# rescue_linea5photo.net
KiCad netlist of a schematic drawn in EAGLE
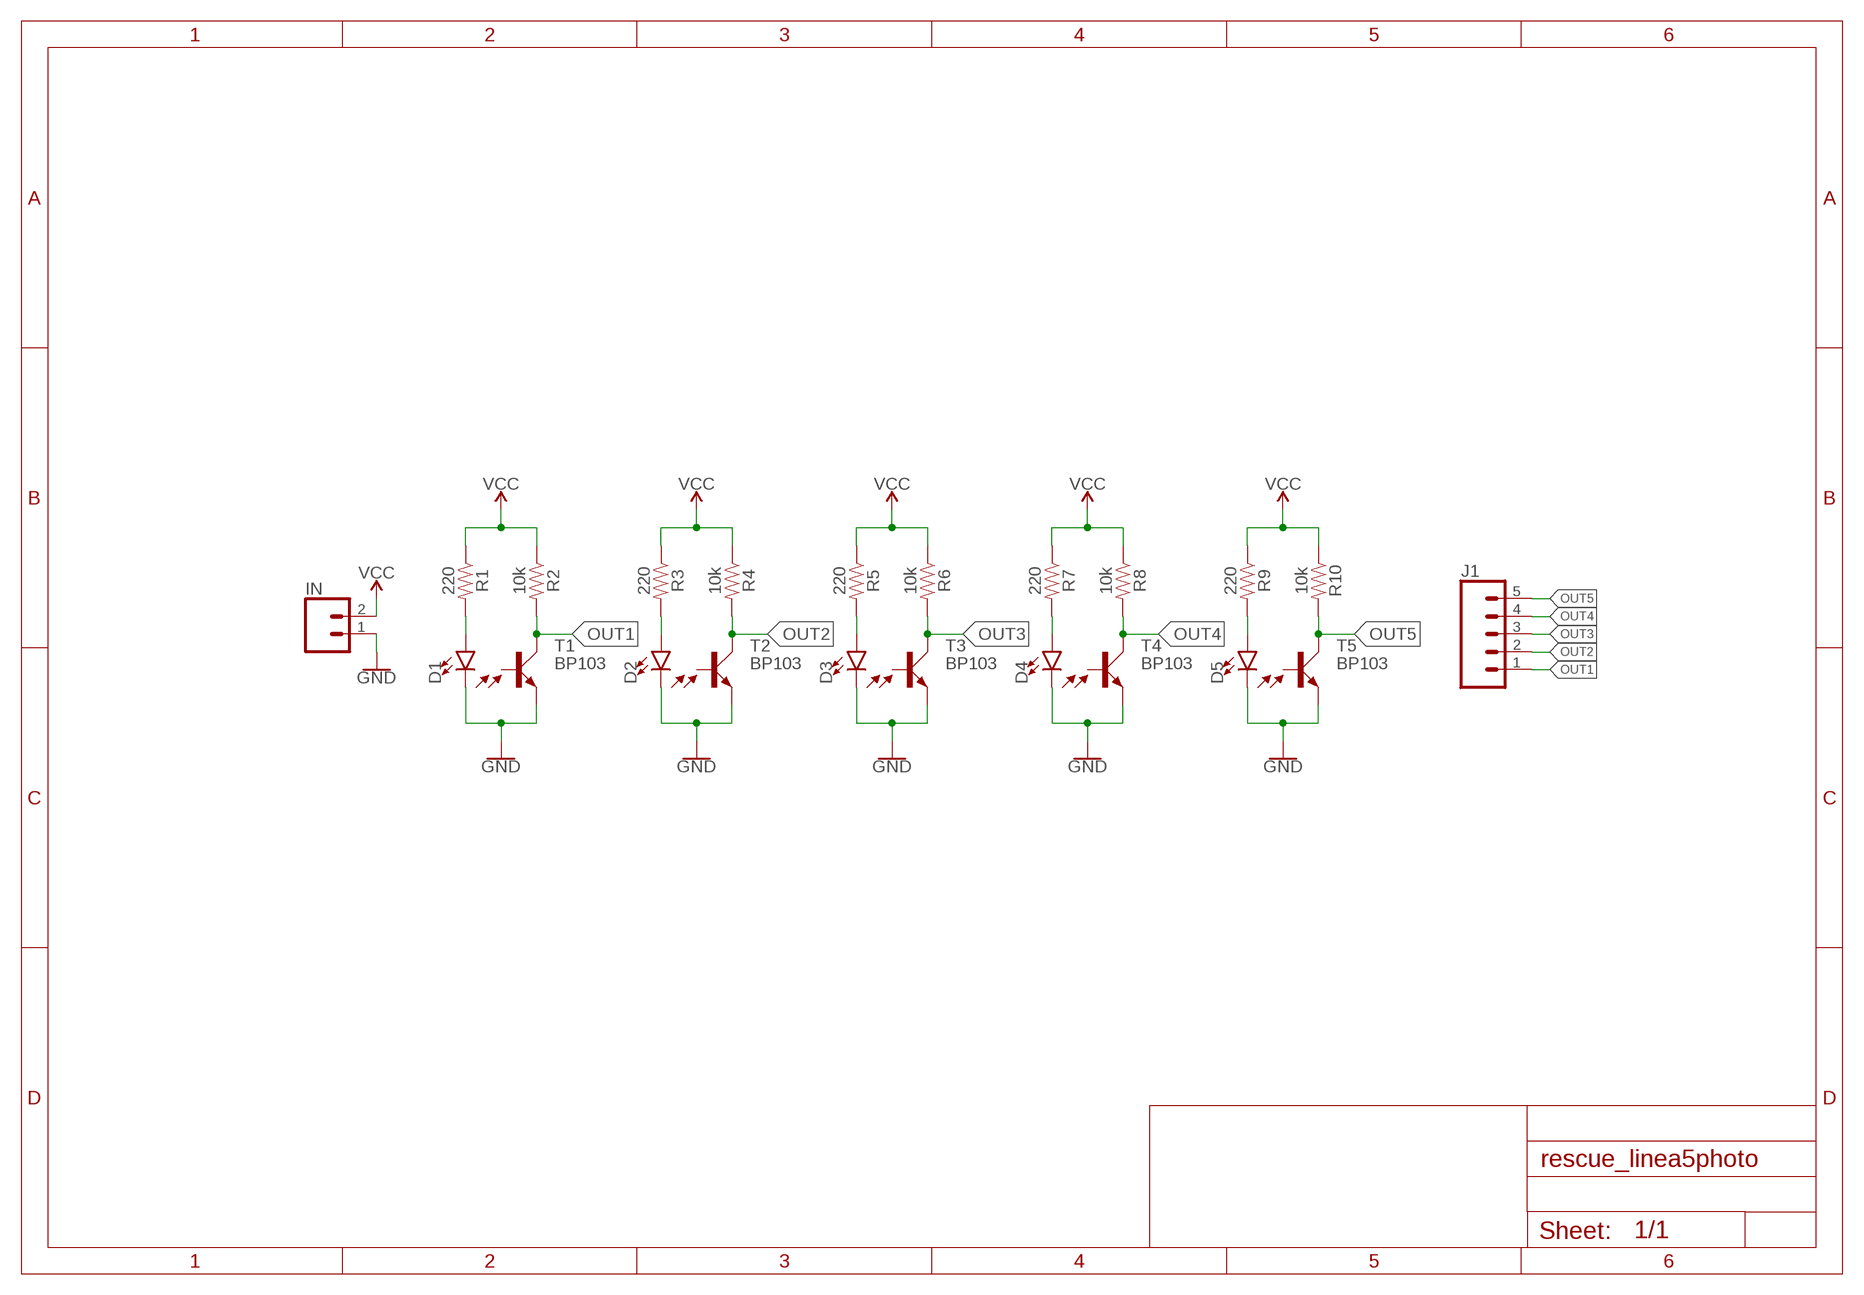
[diagram p0: schematic, sheet 1]

(export (version "E")
  (design (tool "Eeschema 10.0.6"))
  (components
    (comp (ref "D1")
      (value "LED5MM")
      (footprint "eagle-import:LED_5MM")
      (libsource (lib "eagle-import") (part "LED5MM"))
    )
    (comp (ref "D2")
      (value "LED5MM")
      (footprint "eagle-import:LED_5MM")
      (libsource (lib "eagle-import") (part "LED5MM"))
    )
    (comp (ref "D3")
      (value "LED5MM")
      (footprint "eagle-import:LED_5MM")
      (libsource (lib "eagle-import") (part "LED5MM"))
    )
    (comp (ref "D4")
      (value "LED5MM")
      (footprint "eagle-import:LED_5MM")
      (libsource (lib "eagle-import") (part "LED5MM"))
    )
    (comp (ref "D5")
      (value "LED5MM")
      (footprint "eagle-import:LED_5MM")
      (libsource (lib "eagle-import") (part "LED5MM"))
    )
    (comp (ref "IN")
      (value "CONN_02")
      (footprint "eagle-import:1X02")
      (libsource (lib "eagle-import") (part "CONN_02"))
    )
    (comp (ref "J1")
      (value "CONN_05")
      (footprint "eagle-import:1X05")
      (libsource (lib "eagle-import") (part "CONN_05"))
    )
    (comp (ref "R1")
      (value "220")
      (footprint "eagle-import:AXIAL-0.3")
      (libsource (lib "eagle-import") (part "RESISTORAXIAL-0.3"))
    )
    (comp (ref "R2")
      (value "10k")
      (footprint "eagle-import:AXIAL-0.3")
      (libsource (lib "eagle-import") (part "RESISTORAXIAL-0.3"))
    )
    (comp (ref "R3")
      (value "220")
      (footprint "eagle-import:AXIAL-0.3")
      (libsource (lib "eagle-import") (part "RESISTORAXIAL-0.3"))
    )
    (comp (ref "R4")
      (value "10k")
      (footprint "eagle-import:AXIAL-0.3")
      (libsource (lib "eagle-import") (part "RESISTORAXIAL-0.3"))
    )
    (comp (ref "R5")
      (value "220")
      (footprint "eagle-import:AXIAL-0.3")
      (libsource (lib "eagle-import") (part "RESISTORAXIAL-0.3"))
    )
    (comp (ref "R6")
      (value "10k")
      (footprint "eagle-import:AXIAL-0.3")
      (libsource (lib "eagle-import") (part "RESISTORAXIAL-0.3"))
    )
    (comp (ref "R7")
      (value "220")
      (footprint "eagle-import:AXIAL-0.3")
      (libsource (lib "eagle-import") (part "RESISTORAXIAL-0.3"))
    )
    (comp (ref "R8")
      (value "10k")
      (footprint "eagle-import:AXIAL-0.3")
      (libsource (lib "eagle-import") (part "RESISTORAXIAL-0.3"))
    )
    (comp (ref "R9")
      (value "220")
      (footprint "eagle-import:AXIAL-0.3")
      (libsource (lib "eagle-import") (part "RESISTORAXIAL-0.3"))
    )
    (comp (ref "R10")
      (value "10k")
      (footprint "eagle-import:AXIAL-0.3")
      (libsource (lib "eagle-import") (part "RESISTORAXIAL-0.3"))
    )
    (comp (ref "T1")
      (value "BP103")
      (footprint "eagle-import:BP103")
      (libsource (lib "eagle-import") (part "BP103"))
    )
    (comp (ref "T2")
      (value "BP103")
      (footprint "eagle-import:BP103")
      (libsource (lib "eagle-import") (part "BP103"))
    )
    (comp (ref "T3")
      (value "BP103")
      (footprint "eagle-import:BP103")
      (libsource (lib "eagle-import") (part "BP103"))
    )
    (comp (ref "T4")
      (value "BP103")
      (footprint "eagle-import:BP103")
      (libsource (lib "eagle-import") (part "BP103"))
    )
    (comp (ref "T5")
      (value "BP103")
      (footprint "eagle-import:BP103")
      (libsource (lib "eagle-import") (part "BP103"))
    )
  )
  (nets
    (net (code "1") (name "GND") (class "Default")
      (node (ref "D1") (pin "K") (pinfunction "C_K") (pintype "passive"))
      (node (ref "D2") (pin "K") (pinfunction "C_K") (pintype "passive"))
      (node (ref "D3") (pin "K") (pinfunction "C_K") (pintype "passive"))
      (node (ref "D4") (pin "K") (pinfunction "C_K") (pintype "passive"))
      (node (ref "D5") (pin "K") (pinfunction "C_K") (pintype "passive"))
      (node (ref "IN") (pin "1") (pinfunction "1_1") (pintype "passive"))
      (node (ref "T1") (pin "E") (pinfunction "E_E") (pintype "passive"))
      (node (ref "T2") (pin "E") (pinfunction "E_E") (pintype "passive"))
      (node (ref "T3") (pin "E") (pinfunction "E_E") (pintype "passive"))
      (node (ref "T4") (pin "E") (pinfunction "E_E") (pintype "passive"))
      (node (ref "T5") (pin "E") (pinfunction "E_E") (pintype "passive"))
    )
    (net (code "2") (name "Net-(R1-2)") (class "Default")
      (node (ref "D1") (pin "A") (pinfunction "A_A") (pintype "passive"))
      (node (ref "R1") (pin "P$2") (pinfunction "2_P$2") (pintype "passive"))
    )
    (net (code "3") (name "Net-(R3-2)") (class "Default")
      (node (ref "D2") (pin "A") (pinfunction "A_A") (pintype "passive"))
      (node (ref "R3") (pin "P$2") (pinfunction "2_P$2") (pintype "passive"))
    )
    (net (code "4") (name "Net-(R5-2)") (class "Default")
      (node (ref "D3") (pin "A") (pinfunction "A_A") (pintype "passive"))
      (node (ref "R5") (pin "P$2") (pinfunction "2_P$2") (pintype "passive"))
    )
    (net (code "5") (name "Net-(R7-2)") (class "Default")
      (node (ref "D4") (pin "A") (pinfunction "A_A") (pintype "passive"))
      (node (ref "R7") (pin "P$2") (pinfunction "2_P$2") (pintype "passive"))
    )
    (net (code "6") (name "Net-(R9-2)") (class "Default")
      (node (ref "D5") (pin "A") (pinfunction "A_A") (pintype "passive"))
      (node (ref "R9") (pin "P$2") (pinfunction "2_P$2") (pintype "passive"))
    )
    (net (code "7") (name "OUT1") (class "Default")
      (node (ref "J1") (pin "1") (pinfunction "1_1") (pintype "passive"))
      (node (ref "R2") (pin "P$2") (pinfunction "2_P$2") (pintype "passive"))
      (node (ref "T1") (pin "C") (pinfunction "C_C") (pintype "passive"))
    )
    (net (code "8") (name "OUT2") (class "Default")
      (node (ref "J1") (pin "2") (pinfunction "2_2") (pintype "passive"))
      (node (ref "R4") (pin "P$2") (pinfunction "2_P$2") (pintype "passive"))
      (node (ref "T2") (pin "C") (pinfunction "C_C") (pintype "passive"))
    )
    (net (code "9") (name "OUT3") (class "Default")
      (node (ref "J1") (pin "3") (pinfunction "3_3") (pintype "passive"))
      (node (ref "R6") (pin "P$2") (pinfunction "2_P$2") (pintype "passive"))
      (node (ref "T3") (pin "C") (pinfunction "C_C") (pintype "passive"))
    )
    (net (code "10") (name "OUT4") (class "Default")
      (node (ref "J1") (pin "4") (pinfunction "4_4") (pintype "passive"))
      (node (ref "R8") (pin "P$2") (pinfunction "2_P$2") (pintype "passive"))
      (node (ref "T4") (pin "C") (pinfunction "C_C") (pintype "passive"))
    )
    (net (code "11") (name "OUT5") (class "Default")
      (node (ref "J1") (pin "5") (pinfunction "5_5") (pintype "passive"))
      (node (ref "R10") (pin "P$2") (pinfunction "2_P$2") (pintype "passive"))
      (node (ref "T5") (pin "C") (pinfunction "C_C") (pintype "passive"))
    )
    (net (code "12") (name "VCC") (class "Default")
      (node (ref "IN") (pin "2") (pinfunction "2_2") (pintype "passive"))
      (node (ref "R1") (pin "P$1") (pinfunction "1_P$1") (pintype "passive"))
      (node (ref "R10") (pin "P$1") (pinfunction "1_P$1") (pintype "passive"))
      (node (ref "R2") (pin "P$1") (pinfunction "1_P$1") (pintype "passive"))
      (node (ref "R3") (pin "P$1") (pinfunction "1_P$1") (pintype "passive"))
      (node (ref "R4") (pin "P$1") (pinfunction "1_P$1") (pintype "passive"))
      (node (ref "R5") (pin "P$1") (pinfunction "1_P$1") (pintype "passive"))
      (node (ref "R6") (pin "P$1") (pinfunction "1_P$1") (pintype "passive"))
      (node (ref "R7") (pin "P$1") (pinfunction "1_P$1") (pintype "passive"))
      (node (ref "R8") (pin "P$1") (pinfunction "1_P$1") (pintype "passive"))
      (node (ref "R9") (pin "P$1") (pinfunction "1_P$1") (pintype "passive"))
    )
    (net (code "13") (name "unconnected-(T1-PadB)") (class "Default")
      (node (ref "T1") (pin "B") (pinfunction "B_B") (pintype "passive"))
    )
    (net (code "14") (name "unconnected-(T2-PadB)") (class "Default")
      (node (ref "T2") (pin "B") (pinfunction "B_B") (pintype "passive"))
    )
    (net (code "15") (name "unconnected-(T3-PadB)") (class "Default")
      (node (ref "T3") (pin "B") (pinfunction "B_B") (pintype "passive"))
    )
    (net (code "16") (name "unconnected-(T4-PadB)") (class "Default")
      (node (ref "T4") (pin "B") (pinfunction "B_B") (pintype "passive"))
    )
    (net (code "17") (name "unconnected-(T5-PadB)") (class "Default")
      (node (ref "T5") (pin "B") (pinfunction "B_B") (pintype "passive"))
    )
  )
)
